# GSM.net
KiCad netlist of a schematic drawn in Altium Designer
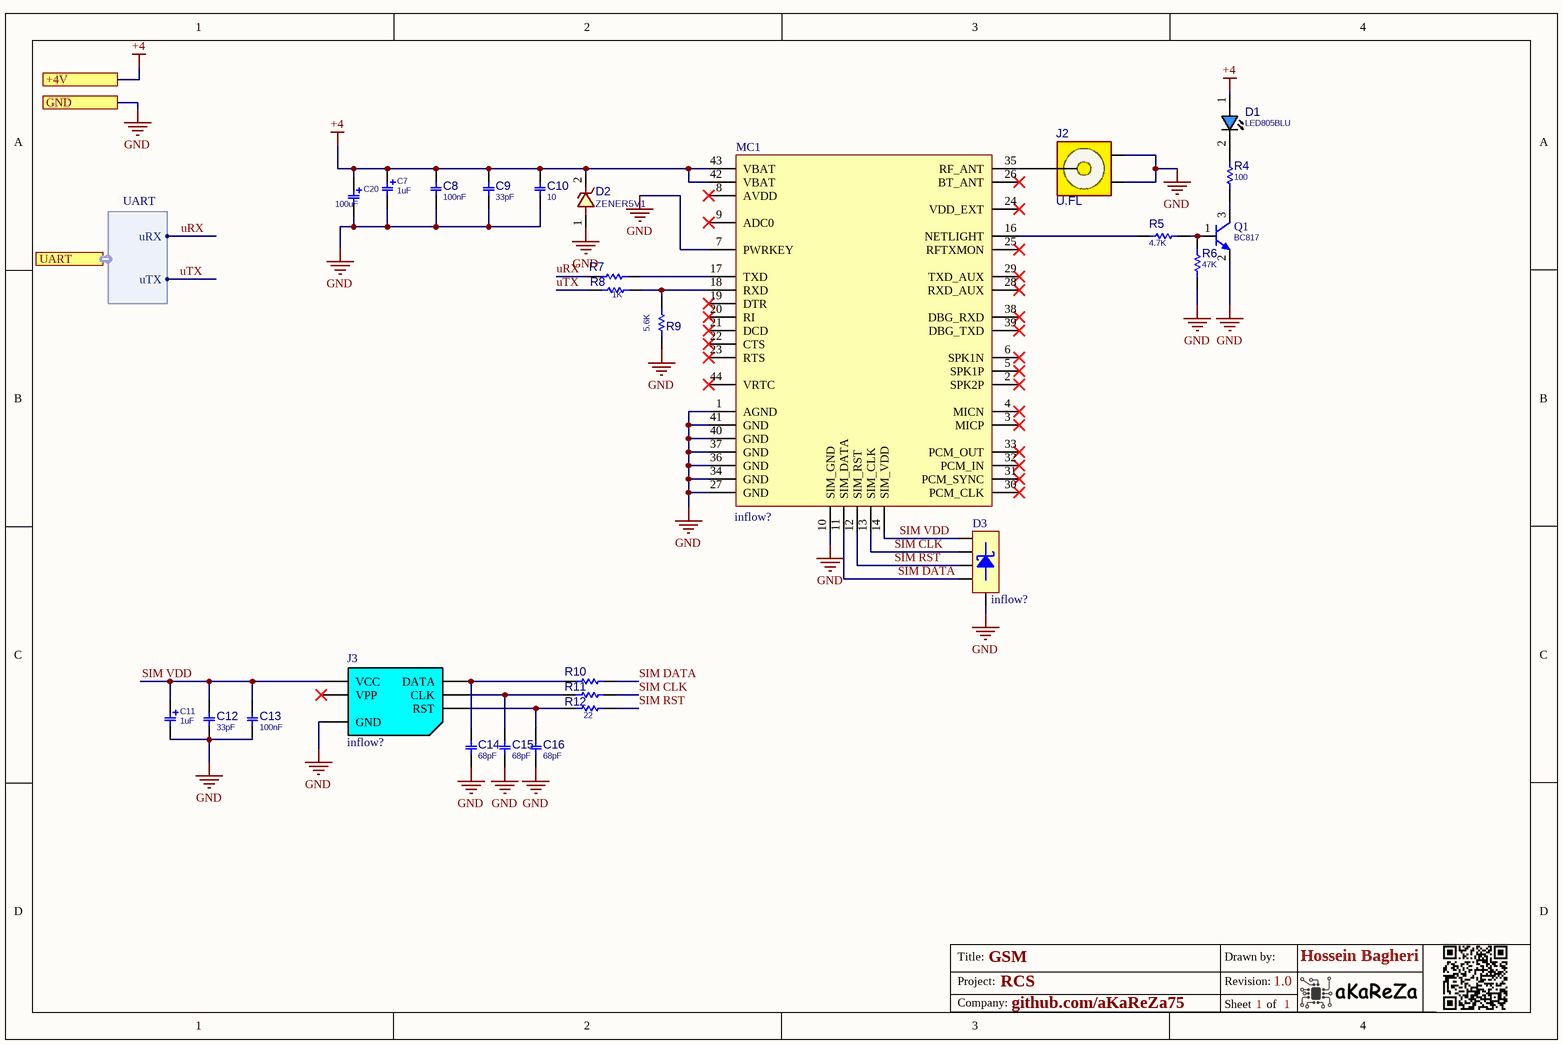
[diagram p0: GSM.SchDoc]

(export (version "E")
  (design (tool "Eeschema 10.0.6"))
  (components
    (comp (ref "C7")
      (value "1uF")
      (footprint "C_TN_2012")
      (description "CAP, SMD, TAN,")
      (libsource (lib "Chila_PCB") (part "CAP_SMD_TAN"))
    )
    (comp (ref "C8")
      (value "100nF")
      (footprint "C0805")
      (description "CAP, MLCC")
      (fields (field (name "MANF_P#") "UMK212ABJ225KG-T") (field (name "MANF") "Taiyo Yuden"))
      (libsource (lib "Chila_PCB") (part "CAP_SMD_MLCC_2.2u50V_0805"))
    )
    (comp (ref "C9")
      (value "33pF")
      (footprint "C0805")
      (description "CAP, MLCC")
      (fields (field (name "MANF_P#") "UMK212ABJ225KG-T") (field (name "MANF") "Taiyo Yuden"))
      (libsource (lib "Chila_PCB") (part "CAP_SMD_MLCC_2.2u50V_0805"))
    )
    (comp (ref "C10")
      (value "10")
      (footprint "C0805")
      (description "CAP, MLCC")
      (fields (field (name "MANF_P#") "UMK212ABJ225KG-T") (field (name "MANF") "Taiyo Yuden"))
      (libsource (lib "Chila_PCB") (part "CAP_SMD_MLCC_2.2u50V_0805"))
    )
    (comp (ref "C11")
      (value "1uF")
      (footprint "C_TN_2012")
      (description "CAP, SMD, TAN,")
      (libsource (lib "Chila_PCB") (part "CAP_SMD_TAN"))
    )
    (comp (ref "C12")
      (value "33pF")
      (footprint "C0805")
      (description "CAP, MLCC")
      (fields (field (name "MANF_P#") "UMK212ABJ225KG-T") (field (name "MANF") "Taiyo Yuden"))
      (libsource (lib "Chila_PCB") (part "CAP_SMD_MLCC_2.2u50V_0805"))
    )
    (comp (ref "C13")
      (value "100nF")
      (footprint "C0805")
      (description "CAP, MLCC")
      (fields (field (name "MANF_P#") "UMK212ABJ225KG-T") (field (name "MANF") "Taiyo Yuden"))
      (libsource (lib "Chila_PCB") (part "CAP_SMD_MLCC_2.2u50V_0805"))
    )
    (comp (ref "C14")
      (value "68pF")
      (footprint "C0805")
      (description "CAP, MLCC")
      (fields (field (name "MANF_P#") "UMK212ABJ225KG-T") (field (name "MANF") "Taiyo Yuden"))
      (libsource (lib "Chila_PCB") (part "CAP_SMD_MLCC_2.2u50V_0805"))
    )
    (comp (ref "C15")
      (value "68pF")
      (footprint "C0805")
      (description "CAP, MLCC")
      (fields (field (name "MANF_P#") "UMK212ABJ225KG-T") (field (name "MANF") "Taiyo Yuden"))
      (libsource (lib "Chila_PCB") (part "CAP_SMD_MLCC_2.2u50V_0805"))
    )
    (comp (ref "C16")
      (value "68pF")
      (footprint "C0805")
      (description "CAP, MLCC")
      (fields (field (name "MANF_P#") "UMK212ABJ225KG-T") (field (name "MANF") "Taiyo Yuden"))
      (libsource (lib "Chila_PCB") (part "CAP_SMD_MLCC_2.2u50V_0805"))
    )
    (comp (ref "C20")
      (value "100uF")
      (footprint "C_TN_3528")
      (description "CAP, SMD, TAN")
      (fields (field (name "MANF") "AVX") (field (name "MANF_P#") "TCJT106M016R0200"))
      (libsource (lib "Chila_PCB") (part "CAP_SMD_TAN_10uF_16V"))
    )
    (comp (ref "D1")
      (value "LED805BLU")
      (footprint "LED0805BLU")
      (description "LED, SMD, 0805, BLUE")
      (fields (field (name "MANF") "MANF") (field (name "MANF_P#") "MANF_PART#"))
      (libsource (lib "Chila_PCB") (part "LED_SMD_0805_BLU"))
    )
    (comp (ref "D2")
      (value "ZENER5V1")
      (footprint "D_SOD123W")
      (description "DIODE, ZENER, 1W, 5.1V")
      (fields (field (name "MANF") "Diodes") (field (name "MANF_P#") "BZT52HC5V1WF-7"))
      (libsource (lib "Chila_PCB") (part "DIODE_SMD_ZENER_BZT52HC5V1"))
    )
    (comp (ref "D3")
      (value "SMF-05")
      (footprint "SC70-5_N")
      (description "TVS Diode Array")
      (fields (field (name "INFLOW") "inflow?") (field (name "VALIDATION") "Valid"))
      (libsource (lib "aKaReZa") (part "Semi_Diod_TVS_SMF05"))
    )
    (comp (ref "J2")
      (value "U.FL")
      (footprint "UFL")
      (description "CONN, RF, U.FL, STRAIGHT, Ultra Miniature Coaxial")
      (fields
        (field (name "MANF_P#") "CONUFL001-SMD, U.FL-R-SMT-1(10), 128-0711-201")
        (field (name "MANF") "Linx, Hirose, Cinch")
      )
      (libsource (lib "Chila_PCB") (part "CONN_RF_UFL"))
    )
    (comp (ref "J3")
      (value "6'Pin")
      (footprint "GCT_SIM8051")
      (description "Nano SimCard Holder 6P")
      (fields (field (name "INFLOW") "inflow?") (field (name "VALIDATION") "Valid"))
      (libsource (lib "aKaReZa") (part "Con_Socket_SimCard_1"))
    )
    (comp (ref "MC1")
      (value "M66")
      (footprint "m66")
      (description "Quectel GSM/GPRS Module")
      (fields (field (name "INFLOW") "inflow?") (field (name "VALIDATION") "Valid"))
      (libsource (lib "aKaReZa") (part "ModSen_Com_M66"))
    )
    (comp (ref "Q1")
      (value "BC817")
      (footprint "SOT23_3")
      (description "BJT, NPN, 45v, 0.5A, SMD, SOT23")
      (fields (field (name "MANF") "NXP, ON"))
      (libsource (lib "Chila_PCB") (part "NPN_BC817_SOT23"))
    )
    (comp (ref "R4")
      (value "100")
      (footprint "R0805")
      (description "RESISTOR, SMD")
      (libsource (lib "Chila_PCB") (part "RES_SMD_0805"))
    )
    (comp (ref "R5")
      (value "4.7K")
      (footprint "R0805")
      (description "RESISTOR, SMD")
      (libsource (lib "Chila_PCB") (part "RES_SMD_0805"))
    )
    (comp (ref "R6")
      (value "47K")
      (footprint "R0805")
      (description "RESISTOR, SMD")
      (libsource (lib "Chila_PCB") (part "RES_SMD_0805"))
    )
    (comp (ref "R7")
      (value "1K")
      (footprint "R0805")
      (description "RESISTOR, SMD")
      (libsource (lib "Chila_PCB") (part "RES_SMD_0805"))
    )
    (comp (ref "R8")
      (value "22")
      (footprint "R0805")
      (description "RESISTOR, SMD")
      (libsource (lib "Chila_PCB") (part "RES_SMD_0805"))
    )
    (comp (ref "R9")
      (value "5.6K")
      (footprint "R0805")
      (description "RESISTOR, SMD")
      (libsource (lib "Chila_PCB") (part "RES_SMD_0805"))
    )
    (comp (ref "R10")
      (value "22")
      (footprint "R0805")
      (description "RESISTOR, SMD")
      (libsource (lib "Chila_PCB") (part "RES_SMD_0805"))
    )
    (comp (ref "R11")
      (value "22")
      (footprint "R0805")
      (description "RESISTOR, SMD")
      (libsource (lib "Chila_PCB") (part "RES_SMD_0805"))
    )
    (comp (ref "R12")
      (value "22")
      (footprint "R0805")
      (description "RESISTOR, SMD")
      (libsource (lib "Chila_PCB") (part "RES_SMD_0805"))
    )
  )
  (nets
    (net (code "2") (name "+4") (class "Default")
      (node (ref "C10") (pin "2") (pinfunction "2_2") (pintype "passive"))
      (node (ref "C20") (pin "1") (pinfunction "1_1") (pintype "passive"))
      (node (ref "C7") (pin "1") (pinfunction "1_1") (pintype "passive"))
      (node (ref "C8") (pin "2") (pinfunction "2_2") (pintype "passive"))
      (node (ref "C9") (pin "2") (pinfunction "2_2") (pintype "passive"))
      (node (ref "D1") (pin "1") (pinfunction "ANODE_1") (pintype "passive"))
      (node (ref "D2") (pin "2") (pinfunction "2_2") (pintype "passive"))
      (node (ref "MC1") (pin "42") (pinfunction "VBAT_42") (pintype "passive"))
      (node (ref "MC1") (pin "43") (pinfunction "VBAT_43") (pintype "passive"))
    )
    (net (code "4") (name "/SIM CLK") (class "Default")
      (node (ref "D3") (pin "4") (pinfunction "K_4") (pintype "passive"))
      (node (ref "MC1") (pin "13") (pinfunction "SIM_CLK_13") (pintype "passive"))
      (node (ref "R11") (pin "1") (pinfunction "1_1") (pintype "passive"))
    )
    (net (code "5") (name "/SIM DATA") (class "Default")
      (node (ref "D3") (pin "5") (pinfunction "K_5") (pintype "passive"))
      (node (ref "MC1") (pin "11") (pinfunction "SIM_DATA_11") (pintype "passive"))
      (node (ref "R10") (pin "1") (pinfunction "1_1") (pintype "passive"))
    )
    (net (code "6") (name "/SIM RST") (class "Default")
      (node (ref "D3") (pin "1") (pinfunction "K_1") (pintype "passive"))
      (node (ref "MC1") (pin "12") (pinfunction "SIM_RST_12") (pintype "passive"))
      (node (ref "R12") (pin "1") (pinfunction "1_1") (pintype "passive"))
    )
    (net (code "7") (name "/SIM VDD") (class "Default")
      (node (ref "C11") (pin "1") (pinfunction "1_1") (pintype "passive"))
      (node (ref "C12") (pin "2") (pinfunction "2_2") (pintype "passive"))
      (node (ref "C13") (pin "2") (pinfunction "2_2") (pintype "passive"))
      (node (ref "D3") (pin "3") (pinfunction "K_3") (pintype "passive"))
      (node (ref "J3") (pin "1") (pinfunction "VCC_1") (pintype "passive"))
      (node (ref "MC1") (pin "14") (pinfunction "SIM_VDD_14") (pintype "passive"))
    )
    (net (code "8") (name "/uRX") (class "Default")
      (node (ref "R7") (pin "2") (pinfunction "2_2") (pintype "passive"))
    )
    (net (code "9") (name "/uTX") (class "Default")
      (node (ref "R8") (pin "2") (pinfunction "2_2") (pintype "passive"))
    )
    (net (code "11") (name "GND") (class "Default")
      (node (ref "C10") (pin "1") (pinfunction "1_1") (pintype "passive"))
      (node (ref "C11") (pin "2") (pinfunction "2_2") (pintype "passive"))
      (node (ref "C12") (pin "1") (pinfunction "1_1") (pintype "passive"))
      (node (ref "C13") (pin "1") (pinfunction "1_1") (pintype "passive"))
      (node (ref "C14") (pin "1") (pinfunction "1_1") (pintype "passive"))
      (node (ref "C15") (pin "1") (pinfunction "1_1") (pintype "passive"))
      (node (ref "C16") (pin "1") (pinfunction "1_1") (pintype "passive"))
      (node (ref "C20") (pin "2") (pinfunction "2_2") (pintype "passive"))
      (node (ref "C7") (pin "2") (pinfunction "2_2") (pintype "passive"))
      (node (ref "C8") (pin "1") (pinfunction "1_1") (pintype "passive"))
      (node (ref "C9") (pin "1") (pinfunction "1_1") (pintype "passive"))
      (node (ref "D2") (pin "1") (pinfunction "1_1") (pintype "passive"))
      (node (ref "D3") (pin "2") (pinfunction "K_2") (pintype "passive"))
      (node (ref "J2") (pin "2") (pinfunction "G1_2") (pintype "passive"))
      (node (ref "J2") (pin "3") (pinfunction "G2_3") (pintype "passive"))
      (node (ref "J3") (pin "5") (pinfunction "GND_5") (pintype "passive"))
      (node (ref "MC1") (pin "1") (pinfunction "AGND_1") (pintype "passive"))
      (node (ref "MC1") (pin "10") (pinfunction "SIM_GND_10") (pintype "passive"))
      (node (ref "MC1") (pin "27") (pinfunction "GND_27") (pintype "passive"))
      (node (ref "MC1") (pin "34") (pinfunction "GND_34") (pintype "passive"))
      (node (ref "MC1") (pin "36") (pinfunction "GND_36") (pintype "passive"))
      (node (ref "MC1") (pin "37") (pinfunction "GND_37") (pintype "passive"))
      (node (ref "MC1") (pin "40") (pinfunction "GND_40") (pintype "passive"))
      (node (ref "MC1") (pin "41") (pinfunction "GND_41") (pintype "passive"))
      (node (ref "MC1") (pin "7") (pinfunction "PWRKEY_7") (pintype "passive"))
      (node (ref "Q1") (pin "2") (pinfunction "E_2") (pintype "passive"))
      (node (ref "R6") (pin "1") (pinfunction "1_1") (pintype "passive"))
      (node (ref "R9") (pin "2") (pinfunction "2_2") (pintype "passive"))
    )
    (net (code "12") (name "Net-(D1-CATHODE)") (class "Default")
      (node (ref "D1") (pin "2") (pinfunction "CATHODE_2") (pintype "passive"))
      (node (ref "R4") (pin "2") (pinfunction "2_2") (pintype "passive"))
    )
    (net (code "13") (name "Net-(J2-SIG)") (class "Default")
      (node (ref "J2") (pin "1") (pinfunction "SIG_1") (pintype "passive"))
      (node (ref "MC1") (pin "35") (pinfunction "RF_ANT_35") (pintype "passive"))
    )
    (net (code "14") (name "Net-(J3-CLK)") (class "Default")
      (node (ref "C15") (pin "2") (pinfunction "2_2") (pintype "passive"))
      (node (ref "J3") (pin "3") (pinfunction "CLK_3") (pintype "passive"))
      (node (ref "R11") (pin "2") (pinfunction "2_2") (pintype "passive"))
    )
    (net (code "15") (name "Net-(J3-DATA)") (class "Default")
      (node (ref "C14") (pin "2") (pinfunction "2_2") (pintype "passive"))
      (node (ref "J3") (pin "4") (pinfunction "DATA_4") (pintype "passive"))
      (node (ref "R10") (pin "2") (pinfunction "2_2") (pintype "passive"))
    )
    (net (code "16") (name "Net-(J3-RST)") (class "Default")
      (node (ref "C16") (pin "2") (pinfunction "2_2") (pintype "passive"))
      (node (ref "J3") (pin "2") (pinfunction "RST_2") (pintype "passive"))
      (node (ref "R12") (pin "2") (pinfunction "2_2") (pintype "passive"))
    )
    (net (code "17") (name "Net-(MC1-NETLIGHT)") (class "Default")
      (node (ref "MC1") (pin "16") (pinfunction "NETLIGHT_16") (pintype "passive"))
      (node (ref "R5") (pin "2") (pinfunction "2_2") (pintype "passive"))
    )
    (net (code "18") (name "Net-(MC1-RXD)") (class "Default")
      (node (ref "MC1") (pin "18") (pinfunction "RXD_18") (pintype "passive"))
      (node (ref "R8") (pin "1") (pinfunction "1_1") (pintype "passive"))
      (node (ref "R9") (pin "1") (pinfunction "1_1") (pintype "passive"))
    )
    (net (code "19") (name "Net-(MC1-TXD)") (class "Default")
      (node (ref "MC1") (pin "17") (pinfunction "TXD_17") (pintype "passive"))
      (node (ref "R7") (pin "1") (pinfunction "1_1") (pintype "passive"))
    )
    (net (code "20") (name "Net-(Q1-B)") (class "Default")
      (node (ref "Q1") (pin "1") (pinfunction "B_1") (pintype "passive"))
      (node (ref "R5") (pin "1") (pinfunction "1_1") (pintype "passive"))
      (node (ref "R6") (pin "2") (pinfunction "2_2") (pintype "passive"))
    )
    (net (code "21") (name "Net-(Q1-C)") (class "Default")
      (node (ref "Q1") (pin "3") (pinfunction "C_3") (pintype "passive"))
      (node (ref "R4") (pin "1") (pinfunction "1_1") (pintype "passive"))
    )
    (net (code "22") (name "unconnected-(J3-VPP-Pad6)") (class "Default")
      (node (ref "J3") (pin "6") (pinfunction "VPP_6") (pintype "passive+no_connect"))
    )
    (net (code "23") (name "unconnected-(MC1-ADC0-Pad9)") (class "Default")
      (node (ref "MC1") (pin "9") (pinfunction "ADC0_9") (pintype "passive+no_connect"))
    )
    (net (code "24") (name "unconnected-(MC1-AVDD-Pad8)") (class "Default")
      (node (ref "MC1") (pin "8") (pinfunction "AVDD_8") (pintype "passive+no_connect"))
    )
    (net (code "25") (name "unconnected-(MC1-BT_ANT-Pad26)") (class "Default")
      (node (ref "MC1") (pin "26") (pinfunction "BT_ANT_26") (pintype "passive+no_connect"))
    )
    (net (code "26") (name "unconnected-(MC1-CTS-Pad22)") (class "Default")
      (node (ref "MC1") (pin "22") (pinfunction "CTS_22") (pintype "passive+no_connect"))
    )
    (net (code "27") (name "unconnected-(MC1-DBG_RXD-Pad38)") (class "Default")
      (node (ref "MC1") (pin "38") (pinfunction "DBG_RXD_38") (pintype "passive+no_connect"))
    )
    (net (code "28") (name "unconnected-(MC1-DBG_TXD-Pad39)") (class "Default")
      (node (ref "MC1") (pin "39") (pinfunction "DBG_TXD_39") (pintype "passive+no_connect"))
    )
    (net (code "29") (name "unconnected-(MC1-DCD-Pad21)") (class "Default")
      (node (ref "MC1") (pin "21") (pinfunction "DCD_21") (pintype "passive+no_connect"))
    )
    (net (code "30") (name "unconnected-(MC1-DTR-Pad19)") (class "Default")
      (node (ref "MC1") (pin "19") (pinfunction "DTR_19") (pintype "passive+no_connect"))
    )
    (net (code "31") (name "unconnected-(MC1-MICN-Pad4)") (class "Default")
      (node (ref "MC1") (pin "4") (pinfunction "MICN_4") (pintype "passive+no_connect"))
    )
    (net (code "32") (name "unconnected-(MC1-MICP-Pad3)") (class "Default")
      (node (ref "MC1") (pin "3") (pinfunction "MICP_3") (pintype "passive+no_connect"))
    )
    (net (code "33") (name "unconnected-(MC1-PCM_CLK-Pad30)") (class "Default")
      (node (ref "MC1") (pin "30") (pinfunction "PCM_CLK_30") (pintype "passive+no_connect"))
    )
    (net (code "34") (name "unconnected-(MC1-PCM_IN-Pad32)") (class "Default")
      (node (ref "MC1") (pin "32") (pinfunction "PCM_IN_32") (pintype "passive+no_connect"))
    )
    (net (code "35") (name "unconnected-(MC1-PCM_OUT-Pad33)") (class "Default")
      (node (ref "MC1") (pin "33") (pinfunction "PCM_OUT_33") (pintype "passive+no_connect"))
    )
    (net (code "36") (name "unconnected-(MC1-PCM_SYNC-Pad31)") (class "Default")
      (node (ref "MC1") (pin "31") (pinfunction "PCM_SYNC_31") (pintype "passive+no_connect"))
    )
    (net (code "37") (name "unconnected-(MC1-RFTXMON-Pad25)") (class "Default")
      (node (ref "MC1") (pin "25") (pinfunction "RFTXMON_25") (pintype "passive+no_connect"))
    )
    (net (code "38") (name "unconnected-(MC1-RI-Pad20)") (class "Default")
      (node (ref "MC1") (pin "20") (pinfunction "RI_20") (pintype "passive+no_connect"))
    )
    (net (code "39") (name "unconnected-(MC1-RTS-Pad23)") (class "Default")
      (node (ref "MC1") (pin "23") (pinfunction "RTS_23") (pintype "passive+no_connect"))
    )
    (net (code "40") (name "unconnected-(MC1-RXD_AUX-Pad28)") (class "Default")
      (node (ref "MC1") (pin "28") (pinfunction "RXD_AUX_28") (pintype "passive+no_connect"))
    )
    (net (code "41") (name "unconnected-(MC1-SPK1N-Pad6)") (class "Default")
      (node (ref "MC1") (pin "6") (pinfunction "SPK1N_6") (pintype "passive+no_connect"))
    )
    (net (code "42") (name "unconnected-(MC1-SPK1P-Pad5)") (class "Default")
      (node (ref "MC1") (pin "5") (pinfunction "SPK1P_5") (pintype "passive+no_connect"))
    )
    (net (code "43") (name "unconnected-(MC1-SPK2P-Pad2)") (class "Default")
      (node (ref "MC1") (pin "2") (pinfunction "SPK2P_2") (pintype "passive+no_connect"))
    )
    (net (code "44") (name "unconnected-(MC1-TXD_AUX-Pad29)") (class "Default")
      (node (ref "MC1") (pin "29") (pinfunction "TXD_AUX_29") (pintype "passive+no_connect"))
    )
    (net (code "45") (name "unconnected-(MC1-VDD_EXT-Pad24)") (class "Default")
      (node (ref "MC1") (pin "24") (pinfunction "VDD_EXT_24") (pintype "passive+no_connect"))
    )
    (net (code "46") (name "unconnected-(MC1-VRTC-Pad44)") (class "Default")
      (node (ref "MC1") (pin "44") (pinfunction "VRTC_44") (pintype "passive+no_connect"))
    )
  )
)
